# Keyless-ESP32.net
KiCad netlist of a schematic drawn in EAGLE
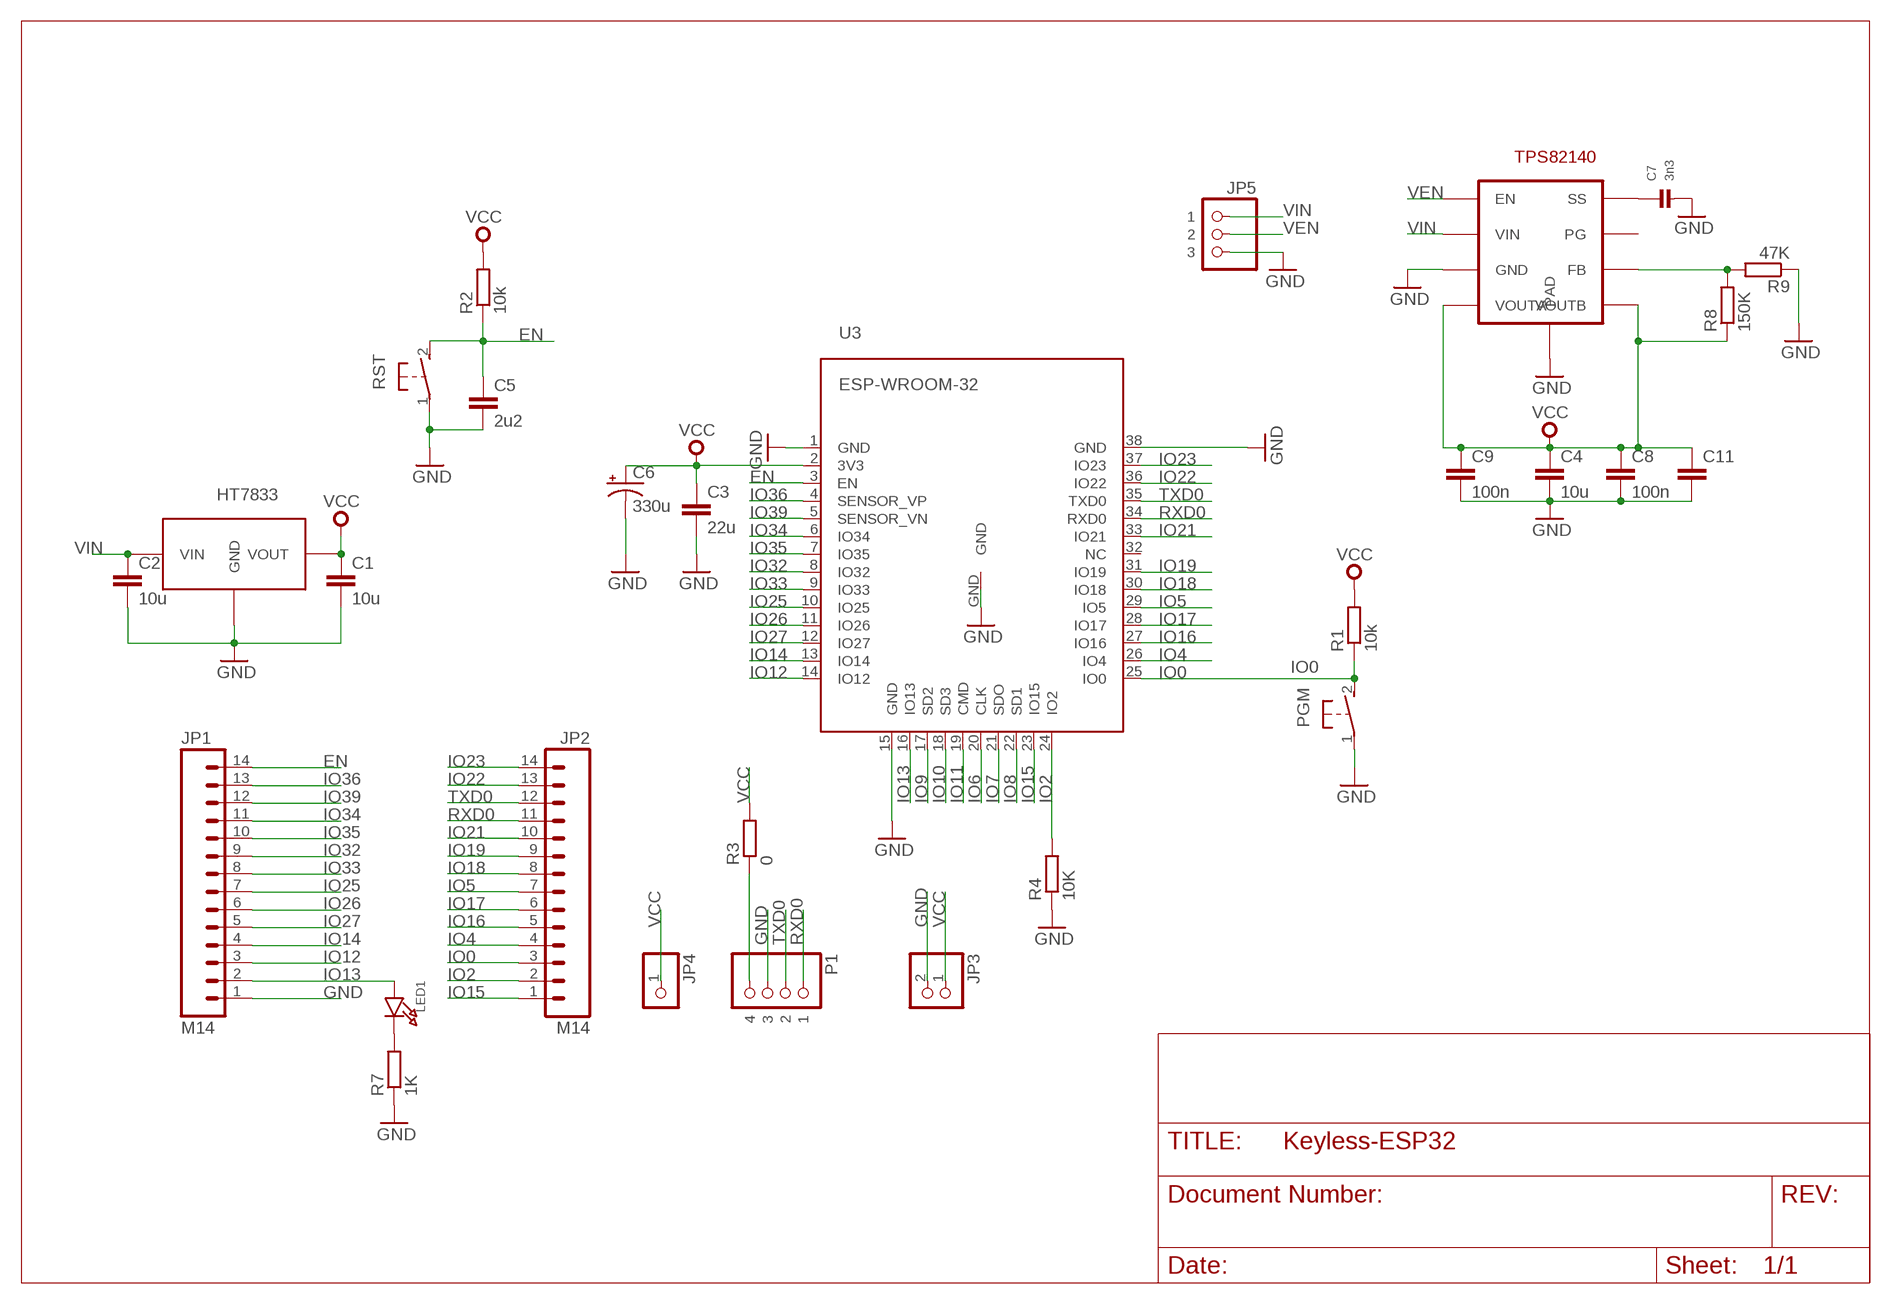
[diagram p0: schematic, sheet 1]

(export (version "E")
  (design (tool "Eeschema 10.0.6"))
  (components
    (comp (ref "C1")
      (value "10u")
      (footprint "eagle-import:C0603")
      (libsource (lib "eagle-import") (part "C-EUC0603"))
    )
    (comp (ref "C2")
      (value "10u")
      (footprint "eagle-import:C0603")
      (libsource (lib "eagle-import") (part "C-EUC0603"))
    )
    (comp (ref "C3")
      (value "22u")
      (footprint "eagle-import:0805")
      (libsource (lib "eagle-import") (part "CAP0805"))
    )
    (comp (ref "C4")
      (value "10u")
      (footprint "eagle-import:C0603")
      (libsource (lib "eagle-import") (part "C-EUC0603"))
    )
    (comp (ref "C5")
      (value "2u2")
      (footprint "eagle-import:C0603")
      (libsource (lib "eagle-import") (part "C-EUC0603"))
    )
    (comp (ref "C6")
      (value "330u")
      (footprint "eagle-import:VISHAY_C")
      (libsource (lib "eagle-import") (part "CAP_POLSMD"))
    )
    (comp (ref "C7")
      (value "3n3")
      (footprint "eagle-import:0603")
      (libsource (lib "eagle-import") (part "CAP_CERAMIC0603"))
    )
    (comp (ref "C8")
      (value "100n")
      (footprint "eagle-import:C0603")
      (libsource (lib "eagle-import") (part "C-EUC0603"))
    )
    (comp (ref "C9")
      (value "100n")
      (footprint "eagle-import:C0603")
      (libsource (lib "eagle-import") (part "C-EUC0603"))
    )
    (comp (ref "C11")
      (value "CAPSMD")
      (footprint "eagle-import:GRM43D")
      (libsource (lib "eagle-import") (part "CAPSMD"))
    )
    (comp (ref "JP1")
      (value "M14")
      (footprint "eagle-import:1X14")
      (libsource (lib "eagle-import") (part "M14"))
    )
    (comp (ref "JP2")
      (value "M14")
      (footprint "eagle-import:1X14")
      (libsource (lib "eagle-import") (part "M14"))
    )
    (comp (ref "JP3")
      (value "HEADER-1X2ROUND")
      (footprint "eagle-import:1X02_ROUND")
      (libsource (lib "eagle-import") (part "HEADER-1X2ROUND"))
    )
    (comp (ref "JP4")
      (value "HEADER-1X1ROUND")
      (footprint "eagle-import:1X01_ROUND")
      (libsource (lib "eagle-import") (part "HEADER-1X1ROUND"))
    )
    (comp (ref "JP5")
      (value "HEADER-1X3ROUND")
      (footprint "eagle-import:1X03_ROUND")
      (libsource (lib "eagle-import") (part "HEADER-1X3ROUND"))
    )
    (comp (ref "LED1")
      (value "LED0603")
      (footprint "eagle-import:CHIPLED_0603")
      (libsource (lib "eagle-import") (part "LED0603"))
    )
    (comp (ref "P1")
      (value "HEADER-1X4ROUND")
      (footprint "eagle-import:1X04_ROUND")
      (libsource (lib "eagle-import") (part "HEADER-1X4ROUND"))
    )
    (comp (ref "PGM")
      (value "DTSM-3")
      (footprint "eagle-import:DTSM-3")
      (libsource (lib "eagle-import") (part "DTSM-3"))
    )
    (comp (ref "R1")
      (value "10k")
      (footprint "eagle-import:R0603")
      (libsource (lib "eagle-import") (part "R-EU_R0603"))
    )
    (comp (ref "R2")
      (value "10k")
      (footprint "eagle-import:R0603")
      (libsource (lib "eagle-import") (part "R-EU_R0603"))
    )
    (comp (ref "R3")
      (value "0")
      (footprint "eagle-import:R0603")
      (libsource (lib "eagle-import") (part "R-EU_R0603"))
    )
    (comp (ref "R4")
      (value "10K")
      (footprint "eagle-import:R0603")
      (libsource (lib "eagle-import") (part "R-EU_R0603"))
    )
    (comp (ref "R7")
      (value "1K")
      (footprint "eagle-import:R0603")
      (libsource (lib "eagle-import") (part "R-EU_R0603"))
    )
    (comp (ref "R8")
      (value "150K")
      (footprint "eagle-import:R0603")
      (libsource (lib "eagle-import") (part "R-EU_R0603"))
    )
    (comp (ref "R9")
      (value "47K")
      (footprint "eagle-import:R0603")
      (libsource (lib "eagle-import") (part "R-EU_R0603"))
    )
    (comp (ref "RST")
      (value "DTSM-3")
      (footprint "eagle-import:DTSM-3")
      (libsource (lib "eagle-import") (part "DTSM-3"))
    )
    (comp (ref "U$1")
      (value "HT7833")
      (footprint "eagle-import:SOT89")
      (libsource (lib "eagle-import") (part "HT7333"))
    )
    (comp (ref "U$2")
      (value "TPS82140")
      (footprint "eagle-import:TPS82140")
      (libsource (lib "eagle-import") (part "TPS82140"))
    )
    (comp (ref "U3")
      (value "ESP-WROOM-32")
      (footprint "eagle-import:ESP-WROOM-32")
      (libsource (lib "eagle-import") (part "ESP-WROOM-32"))
    )
  )
  (nets
    (net (code "1") (name "/EN") (class "Default")
      (node (ref "C5") (pin "1") (pinfunction "1_1") (pintype "passive"))
      (node (ref "JP1") (pin "14") (pinfunction "14_14") (pintype "passive"))
      (node (ref "R2") (pin "1") (pinfunction "1_1") (pintype "passive"))
      (node (ref "RST") (pin "2") (pinfunction "2_2") (pintype "passive"))
      (node (ref "U3") (pin "3") (pinfunction "EN_3") (pintype "bidirectional"))
    )
    (net (code "2") (name "/IO0") (class "Default")
      (node (ref "JP2") (pin "3") (pinfunction "3_3") (pintype "passive"))
      (node (ref "PGM") (pin "2") (pinfunction "2_2") (pintype "passive"))
      (node (ref "R1") (pin "1") (pinfunction "1_1") (pintype "passive"))
      (node (ref "U3") (pin "25") (pinfunction "IO0_25") (pintype "bidirectional"))
    )
    (net (code "3") (name "/IO2") (class "Default")
      (node (ref "JP2") (pin "2") (pinfunction "2_2") (pintype "passive"))
      (node (ref "R4") (pin "2") (pinfunction "2_2") (pintype "passive"))
      (node (ref "U3") (pin "24") (pinfunction "IO2_24") (pintype "bidirectional"))
    )
    (net (code "4") (name "/IO4") (class "Default")
      (node (ref "JP2") (pin "4") (pinfunction "4_4") (pintype "passive"))
      (node (ref "U3") (pin "26") (pinfunction "IO4_26") (pintype "bidirectional"))
    )
    (net (code "5") (name "/IO5") (class "Default")
      (node (ref "JP2") (pin "7") (pinfunction "7_7") (pintype "passive"))
      (node (ref "U3") (pin "29") (pinfunction "IO5_29") (pintype "bidirectional"))
    )
    (net (code "6") (name "/IO6") (class "Default")
      (node (ref "U3") (pin "20") (pinfunction "CLK_20") (pintype "bidirectional"))
    )
    (net (code "7") (name "/IO7") (class "Default")
      (node (ref "U3") (pin "21") (pinfunction "SDO_21") (pintype "bidirectional"))
    )
    (net (code "8") (name "/IO8") (class "Default")
      (node (ref "U3") (pin "22") (pinfunction "SD1_22") (pintype "bidirectional"))
    )
    (net (code "9") (name "/IO9") (class "Default")
      (node (ref "U3") (pin "17") (pinfunction "SD2_17") (pintype "bidirectional"))
    )
    (net (code "10") (name "/IO10") (class "Default")
      (node (ref "U3") (pin "18") (pinfunction "SD3_18") (pintype "bidirectional"))
    )
    (net (code "11") (name "/IO11") (class "Default")
      (node (ref "U3") (pin "19") (pinfunction "CMD_19") (pintype "bidirectional"))
    )
    (net (code "12") (name "/IO12") (class "Default")
      (node (ref "JP1") (pin "3") (pinfunction "3_3") (pintype "passive"))
      (node (ref "U3") (pin "14") (pinfunction "IO12_14") (pintype "bidirectional"))
    )
    (net (code "13") (name "/IO13") (class "Default")
      (node (ref "JP1") (pin "2") (pinfunction "2_2") (pintype "passive"))
      (node (ref "LED1") (pin "A") (pinfunction "A_A") (pintype "passive"))
      (node (ref "U3") (pin "16") (pinfunction "IO13_16") (pintype "bidirectional"))
    )
    (net (code "14") (name "/IO14") (class "Default")
      (node (ref "JP1") (pin "4") (pinfunction "4_4") (pintype "passive"))
      (node (ref "U3") (pin "13") (pinfunction "IO14_13") (pintype "bidirectional"))
    )
    (net (code "15") (name "/IO15") (class "Default")
      (node (ref "JP2") (pin "1") (pinfunction "1_1") (pintype "passive"))
      (node (ref "U3") (pin "23") (pinfunction "IO15_23") (pintype "bidirectional"))
    )
    (net (code "16") (name "/IO16") (class "Default")
      (node (ref "JP2") (pin "5") (pinfunction "5_5") (pintype "passive"))
      (node (ref "U3") (pin "27") (pinfunction "IO16_27") (pintype "bidirectional"))
    )
    (net (code "17") (name "/IO17") (class "Default")
      (node (ref "JP2") (pin "6") (pinfunction "6_6") (pintype "passive"))
      (node (ref "U3") (pin "28") (pinfunction "IO17_28") (pintype "bidirectional"))
    )
    (net (code "18") (name "/IO18") (class "Default")
      (node (ref "JP2") (pin "8") (pinfunction "8_8") (pintype "passive"))
      (node (ref "U3") (pin "30") (pinfunction "IO18_30") (pintype "bidirectional"))
    )
    (net (code "19") (name "/IO19") (class "Default")
      (node (ref "JP2") (pin "9") (pinfunction "9_9") (pintype "passive"))
      (node (ref "U3") (pin "31") (pinfunction "IO19_31") (pintype "bidirectional"))
    )
    (net (code "20") (name "/IO21") (class "Default")
      (node (ref "JP2") (pin "10") (pinfunction "10_10") (pintype "passive"))
      (node (ref "U3") (pin "33") (pinfunction "IO21_33") (pintype "bidirectional"))
    )
    (net (code "21") (name "/IO22") (class "Default")
      (node (ref "JP2") (pin "13") (pinfunction "13_13") (pintype "passive"))
      (node (ref "U3") (pin "36") (pinfunction "IO22_36") (pintype "bidirectional"))
    )
    (net (code "22") (name "/IO23") (class "Default")
      (node (ref "JP2") (pin "14") (pinfunction "14_14") (pintype "passive"))
      (node (ref "U3") (pin "37") (pinfunction "IO23_37") (pintype "bidirectional"))
    )
    (net (code "23") (name "/IO25") (class "Default")
      (node (ref "JP1") (pin "7") (pinfunction "7_7") (pintype "passive"))
      (node (ref "U3") (pin "10") (pinfunction "IO25_10") (pintype "bidirectional"))
    )
    (net (code "24") (name "/IO26") (class "Default")
      (node (ref "JP1") (pin "6") (pinfunction "6_6") (pintype "passive"))
      (node (ref "U3") (pin "11") (pinfunction "IO26_11") (pintype "bidirectional"))
    )
    (net (code "25") (name "/IO27") (class "Default")
      (node (ref "JP1") (pin "5") (pinfunction "5_5") (pintype "passive"))
      (node (ref "U3") (pin "12") (pinfunction "IO27_12") (pintype "bidirectional"))
    )
    (net (code "26") (name "/IO32") (class "Default")
      (node (ref "JP1") (pin "9") (pinfunction "9_9") (pintype "passive"))
      (node (ref "U3") (pin "8") (pinfunction "IO32_8") (pintype "bidirectional"))
    )
    (net (code "27") (name "/IO33") (class "Default")
      (node (ref "JP1") (pin "8") (pinfunction "8_8") (pintype "passive"))
      (node (ref "U3") (pin "9") (pinfunction "IO33_9") (pintype "bidirectional"))
    )
    (net (code "28") (name "/IO34") (class "Default")
      (node (ref "JP1") (pin "11") (pinfunction "11_11") (pintype "passive"))
      (node (ref "U3") (pin "6") (pinfunction "IO34_6") (pintype "bidirectional"))
    )
    (net (code "29") (name "/IO35") (class "Default")
      (node (ref "JP1") (pin "10") (pinfunction "10_10") (pintype "passive"))
      (node (ref "U3") (pin "7") (pinfunction "IO35_7") (pintype "bidirectional"))
    )
    (net (code "30") (name "/IO36") (class "Default")
      (node (ref "JP1") (pin "13") (pinfunction "13_13") (pintype "passive"))
      (node (ref "U3") (pin "4") (pinfunction "SENSOR_VP_4") (pintype "bidirectional"))
    )
    (net (code "31") (name "/IO39") (class "Default")
      (node (ref "JP1") (pin "12") (pinfunction "12_12") (pintype "passive"))
      (node (ref "U3") (pin "5") (pinfunction "SENSOR_VN_5") (pintype "bidirectional"))
    )
    (net (code "32") (name "/RXD0") (class "Default")
      (node (ref "JP2") (pin "11") (pinfunction "11_11") (pintype "passive"))
      (node (ref "P1") (pin "1") (pinfunction "1_1") (pintype "passive"))
      (node (ref "U3") (pin "34") (pinfunction "RXD0_34") (pintype "bidirectional"))
    )
    (net (code "33") (name "/TXD0") (class "Default")
      (node (ref "JP2") (pin "12") (pinfunction "12_12") (pintype "passive"))
      (node (ref "P1") (pin "2") (pinfunction "2_2") (pintype "passive"))
      (node (ref "U3") (pin "35") (pinfunction "TXD0_35") (pintype "bidirectional"))
    )
    (net (code "34") (name "/VEN") (class "Default")
      (node (ref "JP5") (pin "2") (pinfunction "2_2") (pintype "passive"))
      (node (ref "U$2") (pin "P$1") (pinfunction "EN_P$1") (pintype "bidirectional"))
    )
    (net (code "35") (name "/VIN") (class "Default")
      (node (ref "C2") (pin "1") (pinfunction "1_1") (pintype "passive"))
      (node (ref "JP5") (pin "1") (pinfunction "1_1") (pintype "passive"))
      (node (ref "U$1") (pin "VIN") (pinfunction "VIN_VIN") (pintype "bidirectional"))
      (node (ref "U$2") (pin "P$2") (pinfunction "VIN_P$2") (pintype "bidirectional"))
    )
    (net (code "36") (name "GND") (class "Default")
      (node (ref "C1") (pin "2") (pinfunction "2_2") (pintype "passive"))
      (node (ref "C11") (pin "C") (pinfunction "2_C") (pintype "passive"))
      (node (ref "C2") (pin "2") (pinfunction "2_2") (pintype "passive"))
      (node (ref "C3") (pin "2") (pinfunction "2_2") (pintype "passive"))
      (node (ref "C4") (pin "2") (pinfunction "2_2") (pintype "passive"))
      (node (ref "C5") (pin "2") (pinfunction "2_2") (pintype "passive"))
      (node (ref "C6") (pin "-") (pinfunction "-_-") (pintype "passive"))
      (node (ref "C7") (pin "2") (pinfunction "P$2_2") (pintype "passive"))
      (node (ref "C8") (pin "2") (pinfunction "2_2") (pintype "passive"))
      (node (ref "C9") (pin "2") (pinfunction "2_2") (pintype "passive"))
      (node (ref "JP1") (pin "1") (pinfunction "1_1") (pintype "passive"))
      (node (ref "JP3") (pin "2") (pinfunction "2_2") (pintype "passive"))
      (node (ref "JP5") (pin "3") (pinfunction "3_3") (pintype "passive"))
      (node (ref "P1") (pin "3") (pinfunction "3_3") (pintype "passive"))
      (node (ref "PGM") (pin "1") (pinfunction "1_1") (pintype "passive"))
      (node (ref "R4") (pin "1") (pinfunction "1_1") (pintype "passive"))
      (node (ref "R7") (pin "1") (pinfunction "1_1") (pintype "passive"))
      (node (ref "R9") (pin "1") (pinfunction "1_1") (pintype "passive"))
      (node (ref "RST") (pin "1") (pinfunction "1_1") (pintype "passive"))
      (node (ref "U$1") (pin "GND") (pinfunction "GND_GND") (pintype "bidirectional"))
      (node (ref "U$2") (pin "P$3") (pinfunction "GND_P$3") (pintype "bidirectional"))
      (node (ref "U$2") (pin "P$9") (pinfunction "PAD_P$9") (pintype "bidirectional"))
      (node (ref "U3") (pin "1") (pinfunction "GND_1") (pintype "bidirectional"))
      (node (ref "U3") (pin "15") (pinfunction "GND_15") (pintype "bidirectional"))
      (node (ref "U3") (pin "38") (pinfunction "GND_38") (pintype "bidirectional"))
      (node (ref "U3") (pin "GND") (pinfunction "GND_GND") (pintype "bidirectional"))
    )
    (net (code "37") (name "Net-(C7-P$1)") (class "Default")
      (node (ref "C7") (pin "1") (pinfunction "P$1_1") (pintype "passive"))
      (node (ref "U$2") (pin "P$8") (pinfunction "SS_P$8") (pintype "bidirectional"))
    )
    (net (code "38") (name "Net-(LED1-PadC)") (class "Default")
      (node (ref "LED1") (pin "C") (pinfunction "C_C") (pintype "passive"))
      (node (ref "R7") (pin "2") (pinfunction "2_2") (pintype "passive"))
    )
    (net (code "39") (name "Net-(P1-Pad4)") (class "Default")
      (node (ref "P1") (pin "4") (pinfunction "4_4") (pintype "passive"))
      (node (ref "R3") (pin "1") (pinfunction "1_1") (pintype "passive"))
    )
    (net (code "40") (name "Net-(U$2-FB)") (class "Default")
      (node (ref "R8") (pin "2") (pinfunction "2_2") (pintype "passive"))
      (node (ref "R9") (pin "2") (pinfunction "2_2") (pintype "passive"))
      (node (ref "U$2") (pin "P$6") (pinfunction "FB_P$6") (pintype "bidirectional"))
    )
    (net (code "41") (name "VCC") (class "Default")
      (node (ref "C1") (pin "1") (pinfunction "1_1") (pintype "passive"))
      (node (ref "C11") (pin "A") (pinfunction "1_A") (pintype "passive"))
      (node (ref "C3") (pin "1") (pinfunction "1_1") (pintype "passive"))
      (node (ref "C4") (pin "1") (pinfunction "1_1") (pintype "passive"))
      (node (ref "C6") (pin "+") (pinfunction "+_+") (pintype "passive"))
      (node (ref "C8") (pin "1") (pinfunction "1_1") (pintype "passive"))
      (node (ref "C9") (pin "1") (pinfunction "1_1") (pintype "passive"))
      (node (ref "JP3") (pin "1") (pinfunction "1_1") (pintype "passive"))
      (node (ref "JP4") (pin "1") (pinfunction "1_1") (pintype "passive"))
      (node (ref "R1") (pin "2") (pinfunction "2_2") (pintype "passive"))
      (node (ref "R2") (pin "2") (pinfunction "2_2") (pintype "passive"))
      (node (ref "R3") (pin "2") (pinfunction "2_2") (pintype "passive"))
      (node (ref "R8") (pin "1") (pinfunction "1_1") (pintype "passive"))
      (node (ref "U$1") (pin "VOUT") (pinfunction "VOUT_VOUT") (pintype "bidirectional"))
      (node (ref "U$2") (pin "P$4") (pinfunction "VOUTA_P$4") (pintype "bidirectional"))
      (node (ref "U$2") (pin "P$5") (pinfunction "VOUTB_P$5") (pintype "bidirectional"))
      (node (ref "U3") (pin "2") (pinfunction "3V3_2") (pintype "bidirectional"))
    )
    (net (code "42") (name "unconnected-(U$2-PG-PadP$7)") (class "Default")
      (node (ref "U$2") (pin "P$7") (pinfunction "PG_P$7") (pintype "bidirectional"))
    )
    (net (code "43") (name "unconnected-(U3-NC-Pad32)") (class "Default")
      (node (ref "U3") (pin "32") (pinfunction "NC_32") (pintype "bidirectional"))
    )
  )
)
